# UVBoard.net
KiCad netlist of a schematic drawn in EAGLE
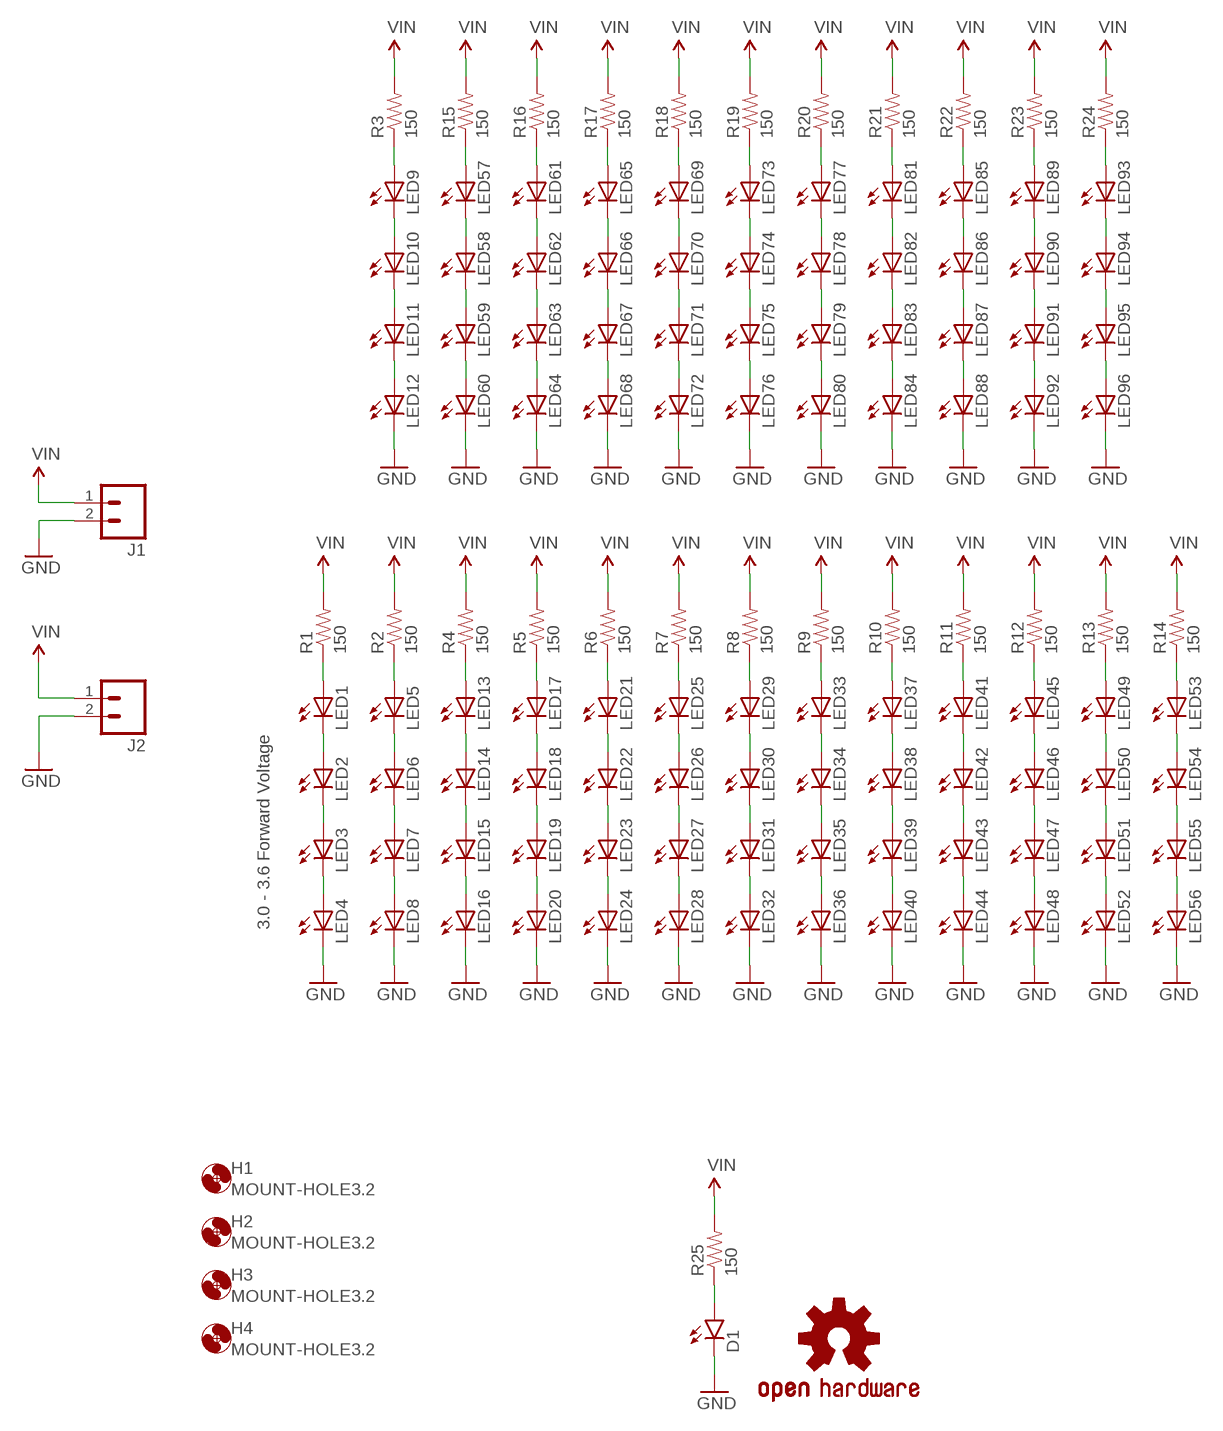
[diagram p0: schematic, sheet 1]

(export (version "E")
  (design (tool "Eeschema 10.0.6"))
  (components
    (comp (ref "D1")
      (value "LED1206-BOTTOM")
      (footprint "eagle-import:LED-1206-BOTTOM")
      (libsource (lib "eagle-import") (part "LED1206-BOTTOM"))
    )
    (comp (ref "H1")
      (value "MOUNT-HOLE3.2")
      (footprint "eagle-import:3,2")
      (libsource (lib "eagle-import") (part "MOUNT-HOLE3.2"))
    )
    (comp (ref "H2")
      (value "MOUNT-HOLE3.2")
      (footprint "eagle-import:3,2")
      (libsource (lib "eagle-import") (part "MOUNT-HOLE3.2"))
    )
    (comp (ref "H3")
      (value "MOUNT-HOLE3.2")
      (footprint "eagle-import:3,2")
      (libsource (lib "eagle-import") (part "MOUNT-HOLE3.2"))
    )
    (comp (ref "H4")
      (value "MOUNT-HOLE3.2")
      (footprint "eagle-import:3,2")
      (libsource (lib "eagle-import") (part "MOUNT-HOLE3.2"))
    )
    (comp (ref "J1")
      (value "M023.5MM")
      (footprint "eagle-import:SCREWTERMINAL-3.5MM-2")
      (libsource (lib "eagle-import") (part "M023.5MM"))
    )
    (comp (ref "J2")
      (value "M023.5MM")
      (footprint "eagle-import:SCREWTERMINAL-3.5MM-2")
      (libsource (lib "eagle-import") (part "M023.5MM"))
    )
    (comp (ref "LED1")
      (value "LEDP-LCC-2")
      (footprint "eagle-import:P-LCC-2")
      (libsource (lib "eagle-import") (part "LEDP-LCC-2"))
    )
    (comp (ref "LED2")
      (value "LEDP-LCC-2")
      (footprint "eagle-import:P-LCC-2")
      (libsource (lib "eagle-import") (part "LEDP-LCC-2"))
    )
    (comp (ref "LED3")
      (value "LEDP-LCC-2")
      (footprint "eagle-import:P-LCC-2")
      (libsource (lib "eagle-import") (part "LEDP-LCC-2"))
    )
    (comp (ref "LED4")
      (value "LEDP-LCC-2")
      (footprint "eagle-import:P-LCC-2")
      (libsource (lib "eagle-import") (part "LEDP-LCC-2"))
    )
    (comp (ref "LED5")
      (value "LEDP-LCC-2")
      (footprint "eagle-import:P-LCC-2")
      (libsource (lib "eagle-import") (part "LEDP-LCC-2"))
    )
    (comp (ref "LED6")
      (value "LEDP-LCC-2")
      (footprint "eagle-import:P-LCC-2")
      (libsource (lib "eagle-import") (part "LEDP-LCC-2"))
    )
    (comp (ref "LED7")
      (value "LEDP-LCC-2")
      (footprint "eagle-import:P-LCC-2")
      (libsource (lib "eagle-import") (part "LEDP-LCC-2"))
    )
    (comp (ref "LED8")
      (value "LEDP-LCC-2")
      (footprint "eagle-import:P-LCC-2")
      (libsource (lib "eagle-import") (part "LEDP-LCC-2"))
    )
    (comp (ref "LED9")
      (value "LEDP-LCC-2")
      (footprint "eagle-import:P-LCC-2")
      (libsource (lib "eagle-import") (part "LEDP-LCC-2"))
    )
    (comp (ref "LED10")
      (value "LEDP-LCC-2")
      (footprint "eagle-import:P-LCC-2")
      (libsource (lib "eagle-import") (part "LEDP-LCC-2"))
    )
    (comp (ref "LED11")
      (value "LEDP-LCC-2")
      (footprint "eagle-import:P-LCC-2")
      (libsource (lib "eagle-import") (part "LEDP-LCC-2"))
    )
    (comp (ref "LED12")
      (value "LEDP-LCC-2")
      (footprint "eagle-import:P-LCC-2")
      (libsource (lib "eagle-import") (part "LEDP-LCC-2"))
    )
    (comp (ref "LED13")
      (value "LEDP-LCC-2")
      (footprint "eagle-import:P-LCC-2")
      (libsource (lib "eagle-import") (part "LEDP-LCC-2"))
    )
    (comp (ref "LED14")
      (value "LEDP-LCC-2")
      (footprint "eagle-import:P-LCC-2")
      (libsource (lib "eagle-import") (part "LEDP-LCC-2"))
    )
    (comp (ref "LED15")
      (value "LEDP-LCC-2")
      (footprint "eagle-import:P-LCC-2")
      (libsource (lib "eagle-import") (part "LEDP-LCC-2"))
    )
    (comp (ref "LED16")
      (value "LEDP-LCC-2")
      (footprint "eagle-import:P-LCC-2")
      (libsource (lib "eagle-import") (part "LEDP-LCC-2"))
    )
    (comp (ref "LED17")
      (value "LEDP-LCC-2")
      (footprint "eagle-import:P-LCC-2")
      (libsource (lib "eagle-import") (part "LEDP-LCC-2"))
    )
    (comp (ref "LED18")
      (value "LEDP-LCC-2")
      (footprint "eagle-import:P-LCC-2")
      (libsource (lib "eagle-import") (part "LEDP-LCC-2"))
    )
    (comp (ref "LED19")
      (value "LEDP-LCC-2")
      (footprint "eagle-import:P-LCC-2")
      (libsource (lib "eagle-import") (part "LEDP-LCC-2"))
    )
    (comp (ref "LED20")
      (value "LEDP-LCC-2")
      (footprint "eagle-import:P-LCC-2")
      (libsource (lib "eagle-import") (part "LEDP-LCC-2"))
    )
    (comp (ref "LED21")
      (value "LEDP-LCC-2")
      (footprint "eagle-import:P-LCC-2")
      (libsource (lib "eagle-import") (part "LEDP-LCC-2"))
    )
    (comp (ref "LED22")
      (value "LEDP-LCC-2")
      (footprint "eagle-import:P-LCC-2")
      (libsource (lib "eagle-import") (part "LEDP-LCC-2"))
    )
    (comp (ref "LED23")
      (value "LEDP-LCC-2")
      (footprint "eagle-import:P-LCC-2")
      (libsource (lib "eagle-import") (part "LEDP-LCC-2"))
    )
    (comp (ref "LED24")
      (value "LEDP-LCC-2")
      (footprint "eagle-import:P-LCC-2")
      (libsource (lib "eagle-import") (part "LEDP-LCC-2"))
    )
    (comp (ref "LED25")
      (value "LEDP-LCC-2")
      (footprint "eagle-import:P-LCC-2")
      (libsource (lib "eagle-import") (part "LEDP-LCC-2"))
    )
    (comp (ref "LED26")
      (value "LEDP-LCC-2")
      (footprint "eagle-import:P-LCC-2")
      (libsource (lib "eagle-import") (part "LEDP-LCC-2"))
    )
    (comp (ref "LED27")
      (value "LEDP-LCC-2")
      (footprint "eagle-import:P-LCC-2")
      (libsource (lib "eagle-import") (part "LEDP-LCC-2"))
    )
    (comp (ref "LED28")
      (value "LEDP-LCC-2")
      (footprint "eagle-import:P-LCC-2")
      (libsource (lib "eagle-import") (part "LEDP-LCC-2"))
    )
    (comp (ref "LED29")
      (value "LEDP-LCC-2")
      (footprint "eagle-import:P-LCC-2")
      (libsource (lib "eagle-import") (part "LEDP-LCC-2"))
    )
    (comp (ref "LED30")
      (value "LEDP-LCC-2")
      (footprint "eagle-import:P-LCC-2")
      (libsource (lib "eagle-import") (part "LEDP-LCC-2"))
    )
    (comp (ref "LED31")
      (value "LEDP-LCC-2")
      (footprint "eagle-import:P-LCC-2")
      (libsource (lib "eagle-import") (part "LEDP-LCC-2"))
    )
    (comp (ref "LED32")
      (value "LEDP-LCC-2")
      (footprint "eagle-import:P-LCC-2")
      (libsource (lib "eagle-import") (part "LEDP-LCC-2"))
    )
    (comp (ref "LED33")
      (value "LEDP-LCC-2")
      (footprint "eagle-import:P-LCC-2")
      (libsource (lib "eagle-import") (part "LEDP-LCC-2"))
    )
    (comp (ref "LED34")
      (value "LEDP-LCC-2")
      (footprint "eagle-import:P-LCC-2")
      (libsource (lib "eagle-import") (part "LEDP-LCC-2"))
    )
    (comp (ref "LED35")
      (value "LEDP-LCC-2")
      (footprint "eagle-import:P-LCC-2")
      (libsource (lib "eagle-import") (part "LEDP-LCC-2"))
    )
    (comp (ref "LED36")
      (value "LEDP-LCC-2")
      (footprint "eagle-import:P-LCC-2")
      (libsource (lib "eagle-import") (part "LEDP-LCC-2"))
    )
    (comp (ref "LED37")
      (value "LEDP-LCC-2")
      (footprint "eagle-import:P-LCC-2")
      (libsource (lib "eagle-import") (part "LEDP-LCC-2"))
    )
    (comp (ref "LED38")
      (value "LEDP-LCC-2")
      (footprint "eagle-import:P-LCC-2")
      (libsource (lib "eagle-import") (part "LEDP-LCC-2"))
    )
    (comp (ref "LED39")
      (value "LEDP-LCC-2")
      (footprint "eagle-import:P-LCC-2")
      (libsource (lib "eagle-import") (part "LEDP-LCC-2"))
    )
    (comp (ref "LED40")
      (value "LEDP-LCC-2")
      (footprint "eagle-import:P-LCC-2")
      (libsource (lib "eagle-import") (part "LEDP-LCC-2"))
    )
    (comp (ref "LED41")
      (value "LEDP-LCC-2")
      (footprint "eagle-import:P-LCC-2")
      (libsource (lib "eagle-import") (part "LEDP-LCC-2"))
    )
    (comp (ref "LED42")
      (value "LEDP-LCC-2")
      (footprint "eagle-import:P-LCC-2")
      (libsource (lib "eagle-import") (part "LEDP-LCC-2"))
    )
    (comp (ref "LED43")
      (value "LEDP-LCC-2")
      (footprint "eagle-import:P-LCC-2")
      (libsource (lib "eagle-import") (part "LEDP-LCC-2"))
    )
    (comp (ref "LED44")
      (value "LEDP-LCC-2")
      (footprint "eagle-import:P-LCC-2")
      (libsource (lib "eagle-import") (part "LEDP-LCC-2"))
    )
    (comp (ref "LED45")
      (value "LEDP-LCC-2")
      (footprint "eagle-import:P-LCC-2")
      (libsource (lib "eagle-import") (part "LEDP-LCC-2"))
    )
    (comp (ref "LED46")
      (value "LEDP-LCC-2")
      (footprint "eagle-import:P-LCC-2")
      (libsource (lib "eagle-import") (part "LEDP-LCC-2"))
    )
    (comp (ref "LED47")
      (value "LEDP-LCC-2")
      (footprint "eagle-import:P-LCC-2")
      (libsource (lib "eagle-import") (part "LEDP-LCC-2"))
    )
    (comp (ref "LED48")
      (value "LEDP-LCC-2")
      (footprint "eagle-import:P-LCC-2")
      (libsource (lib "eagle-import") (part "LEDP-LCC-2"))
    )
    (comp (ref "LED49")
      (value "LEDP-LCC-2")
      (footprint "eagle-import:P-LCC-2")
      (libsource (lib "eagle-import") (part "LEDP-LCC-2"))
    )
    (comp (ref "LED50")
      (value "LEDP-LCC-2")
      (footprint "eagle-import:P-LCC-2")
      (libsource (lib "eagle-import") (part "LEDP-LCC-2"))
    )
    (comp (ref "LED51")
      (value "LEDP-LCC-2")
      (footprint "eagle-import:P-LCC-2")
      (libsource (lib "eagle-import") (part "LEDP-LCC-2"))
    )
    (comp (ref "LED52")
      (value "LEDP-LCC-2")
      (footprint "eagle-import:P-LCC-2")
      (libsource (lib "eagle-import") (part "LEDP-LCC-2"))
    )
    (comp (ref "LED53")
      (value "LEDP-LCC-2")
      (footprint "eagle-import:P-LCC-2")
      (libsource (lib "eagle-import") (part "LEDP-LCC-2"))
    )
    (comp (ref "LED54")
      (value "LEDP-LCC-2")
      (footprint "eagle-import:P-LCC-2")
      (libsource (lib "eagle-import") (part "LEDP-LCC-2"))
    )
    (comp (ref "LED55")
      (value "LEDP-LCC-2")
      (footprint "eagle-import:P-LCC-2")
      (libsource (lib "eagle-import") (part "LEDP-LCC-2"))
    )
    (comp (ref "LED56")
      (value "LEDP-LCC-2")
      (footprint "eagle-import:P-LCC-2")
      (libsource (lib "eagle-import") (part "LEDP-LCC-2"))
    )
    (comp (ref "LED57")
      (value "LEDP-LCC-2")
      (footprint "eagle-import:P-LCC-2")
      (libsource (lib "eagle-import") (part "LEDP-LCC-2"))
    )
    (comp (ref "LED58")
      (value "LEDP-LCC-2")
      (footprint "eagle-import:P-LCC-2")
      (libsource (lib "eagle-import") (part "LEDP-LCC-2"))
    )
    (comp (ref "LED59")
      (value "LEDP-LCC-2")
      (footprint "eagle-import:P-LCC-2")
      (libsource (lib "eagle-import") (part "LEDP-LCC-2"))
    )
    (comp (ref "LED60")
      (value "LEDP-LCC-2")
      (footprint "eagle-import:P-LCC-2")
      (libsource (lib "eagle-import") (part "LEDP-LCC-2"))
    )
    (comp (ref "LED61")
      (value "LEDP-LCC-2")
      (footprint "eagle-import:P-LCC-2")
      (libsource (lib "eagle-import") (part "LEDP-LCC-2"))
    )
    (comp (ref "LED62")
      (value "LEDP-LCC-2")
      (footprint "eagle-import:P-LCC-2")
      (libsource (lib "eagle-import") (part "LEDP-LCC-2"))
    )
    (comp (ref "LED63")
      (value "LEDP-LCC-2")
      (footprint "eagle-import:P-LCC-2")
      (libsource (lib "eagle-import") (part "LEDP-LCC-2"))
    )
    (comp (ref "LED64")
      (value "LEDP-LCC-2")
      (footprint "eagle-import:P-LCC-2")
      (libsource (lib "eagle-import") (part "LEDP-LCC-2"))
    )
    (comp (ref "LED65")
      (value "LEDP-LCC-2")
      (footprint "eagle-import:P-LCC-2")
      (libsource (lib "eagle-import") (part "LEDP-LCC-2"))
    )
    (comp (ref "LED66")
      (value "LEDP-LCC-2")
      (footprint "eagle-import:P-LCC-2")
      (libsource (lib "eagle-import") (part "LEDP-LCC-2"))
    )
    (comp (ref "LED67")
      (value "LEDP-LCC-2")
      (footprint "eagle-import:P-LCC-2")
      (libsource (lib "eagle-import") (part "LEDP-LCC-2"))
    )
    (comp (ref "LED68")
      (value "LEDP-LCC-2")
      (footprint "eagle-import:P-LCC-2")
      (libsource (lib "eagle-import") (part "LEDP-LCC-2"))
    )
    (comp (ref "LED69")
      (value "LEDP-LCC-2")
      (footprint "eagle-import:P-LCC-2")
      (libsource (lib "eagle-import") (part "LEDP-LCC-2"))
    )
    (comp (ref "LED70")
      (value "LEDP-LCC-2")
      (footprint "eagle-import:P-LCC-2")
      (libsource (lib "eagle-import") (part "LEDP-LCC-2"))
    )
    (comp (ref "LED71")
      (value "LEDP-LCC-2")
      (footprint "eagle-import:P-LCC-2")
      (libsource (lib "eagle-import") (part "LEDP-LCC-2"))
    )
    (comp (ref "LED72")
      (value "LEDP-LCC-2")
      (footprint "eagle-import:P-LCC-2")
      (libsource (lib "eagle-import") (part "LEDP-LCC-2"))
    )
    (comp (ref "LED73")
      (value "LEDP-LCC-2")
      (footprint "eagle-import:P-LCC-2")
      (libsource (lib "eagle-import") (part "LEDP-LCC-2"))
    )
    (comp (ref "LED74")
      (value "LEDP-LCC-2")
      (footprint "eagle-import:P-LCC-2")
      (libsource (lib "eagle-import") (part "LEDP-LCC-2"))
    )
    (comp (ref "LED75")
      (value "LEDP-LCC-2")
      (footprint "eagle-import:P-LCC-2")
      (libsource (lib "eagle-import") (part "LEDP-LCC-2"))
    )
    (comp (ref "LED76")
      (value "LEDP-LCC-2")
      (footprint "eagle-import:P-LCC-2")
      (libsource (lib "eagle-import") (part "LEDP-LCC-2"))
    )
    (comp (ref "LED77")
      (value "LEDP-LCC-2")
      (footprint "eagle-import:P-LCC-2")
      (libsource (lib "eagle-import") (part "LEDP-LCC-2"))
    )
    (comp (ref "LED78")
      (value "LEDP-LCC-2")
      (footprint "eagle-import:P-LCC-2")
      (libsource (lib "eagle-import") (part "LEDP-LCC-2"))
    )
    (comp (ref "LED79")
      (value "LEDP-LCC-2")
      (footprint "eagle-import:P-LCC-2")
      (libsource (lib "eagle-import") (part "LEDP-LCC-2"))
    )
    (comp (ref "LED80")
      (value "LEDP-LCC-2")
      (footprint "eagle-import:P-LCC-2")
      (libsource (lib "eagle-import") (part "LEDP-LCC-2"))
    )
    (comp (ref "LED81")
      (value "LEDP-LCC-2")
      (footprint "eagle-import:P-LCC-2")
      (libsource (lib "eagle-import") (part "LEDP-LCC-2"))
    )
    (comp (ref "LED82")
      (value "LEDP-LCC-2")
      (footprint "eagle-import:P-LCC-2")
      (libsource (lib "eagle-import") (part "LEDP-LCC-2"))
    )
    (comp (ref "LED83")
      (value "LEDP-LCC-2")
      (footprint "eagle-import:P-LCC-2")
      (libsource (lib "eagle-import") (part "LEDP-LCC-2"))
    )
    (comp (ref "LED84")
      (value "LEDP-LCC-2")
      (footprint "eagle-import:P-LCC-2")
      (libsource (lib "eagle-import") (part "LEDP-LCC-2"))
    )
    (comp (ref "LED85")
      (value "LEDP-LCC-2")
      (footprint "eagle-import:P-LCC-2")
      (libsource (lib "eagle-import") (part "LEDP-LCC-2"))
    )
    (comp (ref "LED86")
      (value "LEDP-LCC-2")
      (footprint "eagle-import:P-LCC-2")
      (libsource (lib "eagle-import") (part "LEDP-LCC-2"))
    )
    (comp (ref "LED87")
      (value "LEDP-LCC-2")
      (footprint "eagle-import:P-LCC-2")
      (libsource (lib "eagle-import") (part "LEDP-LCC-2"))
    )
    (comp (ref "LED88")
      (value "LEDP-LCC-2")
      (footprint "eagle-import:P-LCC-2")
      (libsource (lib "eagle-import") (part "LEDP-LCC-2"))
    )
    (comp (ref "LED89")
      (value "LEDP-LCC-2")
      (footprint "eagle-import:P-LCC-2")
      (libsource (lib "eagle-import") (part "LEDP-LCC-2"))
    )
    (comp (ref "LED90")
      (value "LEDP-LCC-2")
      (footprint "eagle-import:P-LCC-2")
      (libsource (lib "eagle-import") (part "LEDP-LCC-2"))
    )
    (comp (ref "LED91")
      (value "LEDP-LCC-2")
      (footprint "eagle-import:P-LCC-2")
      (libsource (lib "eagle-import") (part "LEDP-LCC-2"))
    )
    (comp (ref "LED92")
      (value "LEDP-LCC-2")
      (footprint "eagle-import:P-LCC-2")
      (libsource (lib "eagle-import") (part "LEDP-LCC-2"))
    )
    (comp (ref "LED93")
      (value "LEDP-LCC-2")
      (footprint "eagle-import:P-LCC-2")
      (libsource (lib "eagle-import") (part "LEDP-LCC-2"))
    )
    (comp (ref "LED94")
      (value "LEDP-LCC-2")
      (footprint "eagle-import:P-LCC-2")
      (libsource (lib "eagle-import") (part "LEDP-LCC-2"))
    )
    (comp (ref "LED95")
      (value "LEDP-LCC-2")
      (footprint "eagle-import:P-LCC-2")
      (libsource (lib "eagle-import") (part "LEDP-LCC-2"))
    )
    (comp (ref "LED96")
      (value "LEDP-LCC-2")
      (footprint "eagle-import:P-LCC-2")
      (libsource (lib "eagle-import") (part "LEDP-LCC-2"))
    )
    (comp (ref "LOGO1")
      (value "OSHW-LOGOM")
      (footprint "eagle-import:OSHW-LOGO-M")
      (libsource (lib "eagle-import") (part "OSHW-LOGOM"))
    )
    (comp (ref "R1")
      (value "150")
      (footprint "eagle-import:1206")
      (libsource (lib "eagle-import") (part "RESISTOR1206"))
    )
    (comp (ref "R2")
      (value "150")
      (footprint "eagle-import:1206")
      (libsource (lib "eagle-import") (part "RESISTOR1206"))
    )
    (comp (ref "R3")
      (value "150")
      (footprint "eagle-import:1206")
      (libsource (lib "eagle-import") (part "RESISTOR1206"))
    )
    (comp (ref "R4")
      (value "150")
      (footprint "eagle-import:1206")
      (libsource (lib "eagle-import") (part "RESISTOR1206"))
    )
    (comp (ref "R5")
      (value "150")
      (footprint "eagle-import:1206")
      (libsource (lib "eagle-import") (part "RESISTOR1206"))
    )
    (comp (ref "R6")
      (value "150")
      (footprint "eagle-import:1206")
      (libsource (lib "eagle-import") (part "RESISTOR1206"))
    )
    (comp (ref "R7")
      (value "150")
      (footprint "eagle-import:1206")
      (libsource (lib "eagle-import") (part "RESISTOR1206"))
    )
    (comp (ref "R8")
      (value "150")
      (footprint "eagle-import:1206")
      (libsource (lib "eagle-import") (part "RESISTOR1206"))
    )
    (comp (ref "R9")
      (value "150")
      (footprint "eagle-import:1206")
      (libsource (lib "eagle-import") (part "RESISTOR1206"))
    )
    (comp (ref "R10")
      (value "150")
      (footprint "eagle-import:1206")
      (libsource (lib "eagle-import") (part "RESISTOR1206"))
    )
    (comp (ref "R11")
      (value "150")
      (footprint "eagle-import:1206")
      (libsource (lib "eagle-import") (part "RESISTOR1206"))
    )
    (comp (ref "R12")
      (value "150")
      (footprint "eagle-import:1206")
      (libsource (lib "eagle-import") (part "RESISTOR1206"))
    )
    (comp (ref "R13")
      (value "150")
      (footprint "eagle-import:1206")
      (libsource (lib "eagle-import") (part "RESISTOR1206"))
    )
    (comp (ref "R14")
      (value "150")
      (footprint "eagle-import:1206")
      (libsource (lib "eagle-import") (part "RESISTOR1206"))
    )
    (comp (ref "R15")
      (value "150")
      (footprint "eagle-import:1206")
      (libsource (lib "eagle-import") (part "RESISTOR1206"))
    )
    (comp (ref "R16")
      (value "150")
      (footprint "eagle-import:1206")
      (libsource (lib "eagle-import") (part "RESISTOR1206"))
    )
    (comp (ref "R17")
      (value "150")
      (footprint "eagle-import:1206")
      (libsource (lib "eagle-import") (part "RESISTOR1206"))
    )
    (comp (ref "R18")
      (value "150")
      (footprint "eagle-import:1206")
      (libsource (lib "eagle-import") (part "RESISTOR1206"))
    )
    (comp (ref "R19")
      (value "150")
      (footprint "eagle-import:1206")
      (libsource (lib "eagle-import") (part "RESISTOR1206"))
    )
    (comp (ref "R20")
      (value "150")
      (footprint "eagle-import:1206")
      (libsource (lib "eagle-import") (part "RESISTOR1206"))
    )
    (comp (ref "R21")
      (value "150")
      (footprint "eagle-import:1206")
      (libsource (lib "eagle-import") (part "RESISTOR1206"))
    )
    (comp (ref "R22")
      (value "150")
      (footprint "eagle-import:1206")
      (libsource (lib "eagle-import") (part "RESISTOR1206"))
    )
    (comp (ref "R23")
      (value "150")
      (footprint "eagle-import:1206")
      (libsource (lib "eagle-import") (part "RESISTOR1206"))
    )
    (comp (ref "R24")
      (value "150")
      (footprint "eagle-import:1206")
      (libsource (lib "eagle-import") (part "RESISTOR1206"))
    )
    (comp (ref "R25")
      (value "150")
      (footprint "eagle-import:1206")
      (libsource (lib "eagle-import") (part "RESISTOR1206"))
    )
  )
  (nets
    (net (code "1") (name "GND") (class "Default")
      (node (ref "D1") (pin "C") (pinfunction "C_C") (pintype "passive"))
      (node (ref "J1") (pin "2") (pinfunction "2_2") (pintype "passive"))
      (node (ref "J2") (pin "2") (pinfunction "2_2") (pintype "passive"))
      (node (ref "LED12") (pin "C") (pinfunction "C_C") (pintype "passive"))
      (node (ref "LED16") (pin "C") (pinfunction "C_C") (pintype "passive"))
      (node (ref "LED20") (pin "C") (pinfunction "C_C") (pintype "passive"))
      (node (ref "LED24") (pin "C") (pinfunction "C_C") (pintype "passive"))
      (node (ref "LED28") (pin "C") (pinfunction "C_C") (pintype "passive"))
      (node (ref "LED32") (pin "C") (pinfunction "C_C") (pintype "passive"))
      (node (ref "LED36") (pin "C") (pinfunction "C_C") (pintype "passive"))
      (node (ref "LED4") (pin "C") (pinfunction "C_C") (pintype "passive"))
      (node (ref "LED40") (pin "C") (pinfunction "C_C") (pintype "passive"))
      (node (ref "LED44") (pin "C") (pinfunction "C_C") (pintype "passive"))
      (node (ref "LED48") (pin "C") (pinfunction "C_C") (pintype "passive"))
      (node (ref "LED52") (pin "C") (pinfunction "C_C") (pintype "passive"))
      (node (ref "LED56") (pin "C") (pinfunction "C_C") (pintype "passive"))
      (node (ref "LED60") (pin "C") (pinfunction "C_C") (pintype "passive"))
      (node (ref "LED64") (pin "C") (pinfunction "C_C") (pintype "passive"))
      (node (ref "LED68") (pin "C") (pinfunction "C_C") (pintype "passive"))
      (node (ref "LED72") (pin "C") (pinfunction "C_C") (pintype "passive"))
      (node (ref "LED76") (pin "C") (pinfunction "C_C") (pintype "passive"))
      (node (ref "LED8") (pin "C") (pinfunction "C_C") (pintype "passive"))
      (node (ref "LED80") (pin "C") (pinfunction "C_C") (pintype "passive"))
      (node (ref "LED84") (pin "C") (pinfunction "C_C") (pintype "passive"))
      (node (ref "LED88") (pin "C") (pinfunction "C_C") (pintype "passive"))
      (node (ref "LED92") (pin "C") (pinfunction "C_C") (pintype "passive"))
      (node (ref "LED96") (pin "C") (pinfunction "C_C") (pintype "passive"))
    )
    (net (code "2") (name "Net-(D1-PadA)") (class "Default")
      (node (ref "D1") (pin "A") (pinfunction "A_A") (pintype "passive"))
      (node (ref "R25") (pin "1") (pinfunction "1_1") (pintype "passive"))
    )
    (net (code "3") (name "Net-(LED1-PadA)") (class "Default")
      (node (ref "LED1") (pin "A") (pinfunction "A_A") (pintype "passive"))
      (node (ref "R1") (pin "1") (pinfunction "1_1") (pintype "passive"))
    )
    (net (code "4") (name "Net-(LED1-PadC)") (class "Default")
      (node (ref "LED1") (pin "C") (pinfunction "C_C") (pintype "passive"))
      (node (ref "LED2") (pin "A") (pinfunction "A_A") (pintype "passive"))
    )
    (net (code "5") (name "Net-(LED2-PadC)") (class "Default")
      (node (ref "LED2") (pin "C") (pinfunction "C_C") (pintype "passive"))
      (node (ref "LED3") (pin "A") (pinfunction "A_A") (pintype "passive"))
    )
    (net (code "6") (name "Net-(LED3-PadC)") (class "Default")
      (node (ref "LED3") (pin "C") (pinfunction "C_C") (pintype "passive"))
      (node (ref "LED4") (pin "A") (pinfunction "A_A") (pintype "passive"))
    )
    (net (code "7") (name "Net-(LED5-PadA)") (class "Default")
      (node (ref "LED5") (pin "A") (pinfunction "A_A") (pintype "passive"))
      (node (ref "R2") (pin "1") (pinfunction "1_1") (pintype "passive"))
    )
    (net (code "8") (name "Net-(LED5-PadC)") (class "Default")
      (node (ref "LED5") (pin "C") (pinfunction "C_C") (pintype "passive"))
      (node (ref "LED6") (pin "A") (pinfunction "A_A") (pintype "passive"))
    )
    (net (code "9") (name "Net-(LED6-PadC)") (class "Default")
      (node (ref "LED6") (pin "C") (pinfunction "C_C") (pintype "passive"))
      (node (ref "LED7") (pin "A") (pinfunction "A_A") (pintype "passive"))
    )
    (net (code "10") (name "Net-(LED7-PadC)") (class "Default")
      (node (ref "LED7") (pin "C") (pinfunction "C_C") (pintype "passive"))
      (node (ref "LED8") (pin "A") (pinfunction "A_A") (pintype "passive"))
    )
    (net (code "11") (name "Net-(LED9-PadA)") (class "Default")
      (node (ref "LED9") (pin "A") (pinfunction "A_A") (pintype "passive"))
      (node (ref "R3") (pin "1") (pinfunction "1_1") (pintype "passive"))
    )
    (net (code "12") (name "Net-(LED10-PadA)") (class "Default")
      (node (ref "LED10") (pin "A") (pinfunction "A_A") (pintype "passive"))
      (node (ref "LED9") (pin "C") (pinfunction "C_C") (pintype "passive"))
    )
    (net (code "13") (name "Net-(LED10-PadC)") (class "Default")
      (node (ref "LED10") (pin "C") (pinfunction "C_C") (pintype "passive"))
      (node (ref "LED11") (pin "A") (pinfunction "A_A") (pintype "passive"))
    )
    (net (code "14") (name "Net-(LED11-PadC)") (class "Default")
      (node (ref "LED11") (pin "C") (pinfunction "C_C") (pintype "passive"))
      (node (ref "LED12") (pin "A") (pinfunction "A_A") (pintype "passive"))
    )
    (net (code "15") (name "Net-(LED13-PadA)") (class "Default")
      (node (ref "LED13") (pin "A") (pinfunction "A_A") (pintype "passive"))
      (node (ref "R4") (pin "1") (pinfunction "1_1") (pintype "passive"))
    )
    (net (code "16") (name "Net-(LED13-PadC)") (class "Default")
      (node (ref "LED13") (pin "C") (pinfunction "C_C") (pintype "passive"))
      (node (ref "LED14") (pin "A") (pinfunction "A_A") (pintype "passive"))
    )
    (net (code "17") (name "Net-(LED14-PadC)") (class "Default")
      (node (ref "LED14") (pin "C") (pinfunction "C_C") (pintype "passive"))
      (node (ref "LED15") (pin "A") (pinfunction "A_A") (pintype "passive"))
    )
    (net (code "18") (name "Net-(LED15-PadC)") (class "Default")
      (node (ref "LED15") (pin "C") (pinfunction "C_C") (pintype "passive"))
      (node (ref "LED16") (pin "A") (pinfunction "A_A") (pintype "passive"))
    )
    (net (code "19") (name "Net-(LED17-PadA)") (class "Default")
      (node (ref "LED17") (pin "A") (pinfunction "A_A") (pintype "passive"))
      (node (ref "R5") (pin "1") (pinfunction "1_1") (pintype "passive"))
    )
    (net (code "20") (name "Net-(LED17-PadC)") (class "Default")
      (node (ref "LED17") (pin "C") (pinfunction "C_C") (pintype "passive"))
      (node (ref "LED18") (pin "A") (pinfunction "A_A") (pintype "passive"))
    )
    (net (code "21") (name "Net-(LED18-PadC)") (class "Default")
      (node (ref "LED18") (pin "C") (pinfunction "C_C") (pintype "passive"))
      (node (ref "LED19") (pin "A") (pinfunction "A_A") (pintype "passive"))
    )
    (net (code "22") (name "Net-(LED19-PadC)") (class "Default")
      (node (ref "LED19") (pin "C") (pinfunction "C_C") (pintype "passive"))
      (node (ref "LED20") (pin "A") (pinfunction "A_A") (pintype "passive"))
    )
    (net (code "23") (name "Net-(LED21-PadA)") (class "Default")
      (node (ref "LED21") (pin "A") (pinfunction "A_A") (pintype "passive"))
      (node (ref "R6") (pin "1") (pinfunction "1_1") (pintype "passive"))
    )
    (net (code "24") (name "Net-(LED21-PadC)") (class "Default")
      (node (ref "LED21") (pin "C") (pinfunction "C_C") (pintype "passive"))
      (node (ref "LED22") (pin "A") (pinfunction "A_A") (pintype "passive"))
    )
    (net (code "25") (name "Net-(LED22-PadC)") (class "Default")
      (node (ref "LED22") (pin "C") (pinfunction "C_C") (pintype "passive"))
      (node (ref "LED23") (pin "A") (pinfunction "A_A") (pintype "passive"))
    )
    (net (code "26") (name "Net-(LED23-PadC)") (class "Default")
      (node (ref "LED23") (pin "C") (pinfunction "C_C") (pintype "passive"))
      (node (ref "LED24") (pin "A") (pinfunction "A_A") (pintype "passive"))
    )
    (net (code "27") (name "Net-(LED25-PadA)") (class "Default")
      (node (ref "LED25") (pin "A") (pinfunction "A_A") (pintype "passive"))
      (node (ref "R7") (pin "1") (pinfunction "1_1") (pintype "passive"))
    )
    (net (code "28") (name "Net-(LED25-PadC)") (class "Default")
      (node (ref "LED25") (pin "C") (pinfunction "C_C") (pintype "passive"))
      (node (ref "LED26") (pin "A") (pinfunction "A_A") (pintype "passive"))
    )
    (net (code "29") (name "Net-(LED26-PadC)") (class "Default")
      (node (ref "LED26") (pin "C") (pinfunction "C_C") (pintype "passive"))
      (node (ref "LED27") (pin "A") (pinfunction "A_A") (pintype "passive"))
    )
    (net (code "30") (name "Net-(LED27-PadC)") (class "Default")
      (node (ref "LED27") (pin "C") (pinfunction "C_C") (pintype "passive"))
      (node (ref "LED28") (pin "A") (pinfunction "A_A") (pintype "passive"))
    )
    (net (code "31") (name "Net-(LED29-PadA)") (class "Default")
      (node (ref "LED29") (pin "A") (pinfunction "A_A") (pintype "passive"))
      (node (ref "R8") (pin "1") (pinfunction "1_1") (pintype "passive"))
    )
    (net (code "32") (name "Net-(LED29-PadC)") (class "Default")
      (node (ref "LED29") (pin "C") (pinfunction "C_C") (pintype "passive"))
      (node (ref "LED30") (pin "A") (pinfunction "A_A") (pintype "passive"))
    )
    (net (code "33") (name "Net-(LED30-PadC)") (class "Default")
      (node (ref "LED30") (pin "C") (pinfunction "C_C") (pintype "passive"))
      (node (ref "LED31") (pin "A") (pinfunction "A_A") (pintype "passive"))
    )
    (net (code "34") (name "Net-(LED31-PadC)") (class "Default")
      (node (ref "LED31") (pin "C") (pinfunction "C_C") (pintype "passive"))
      (node (ref "LED32") (pin "A") (pinfunction "A_A") (pintype "passive"))
    )
    (net (code "35") (name "Net-(LED33-PadA)") (class "Default")
      (node (ref "LED33") (pin "A") (pinfunction "A_A") (pintype "passive"))
      (node (ref "R9") (pin "1") (pinfunction "1_1") (pintype "passive"))
    )
    (net (code "36") (name "Net-(LED33-PadC)") (class "Default")
      (node (ref "LED33") (pin "C") (pinfunction "C_C") (pintype "passive"))
      (node (ref "LED34") (pin "A") (pinfunction "A_A") (pintype "passive"))
    )
    (net (code "37") (name "Net-(LED34-PadC)") (class "Default")
      (node (ref "LED34") (pin "C") (pinfunction "C_C") (pintype "passive"))
      (node (ref "LED35") (pin "A") (pinfunction "A_A") (pintype "passive"))
    )
    (net (code "38") (name "Net-(LED35-PadC)") (class "Default")
      (node (ref "LED35") (pin "C") (pinfunction "C_C") (pintype "passive"))
      (node (ref "LED36") (pin "A") (pinfunction "A_A") (pintype "passive"))
    )
    (net (code "39") (name "Net-(LED37-PadA)") (class "Default")
      (node (ref "LED37") (pin "A") (pinfunction "A_A") (pintype "passive"))
      (node (ref "R10") (pin "1") (pinfunction "1_1") (pintype "passive"))
    )
    (net (code "40") (name "Net-(LED37-PadC)") (class "Default")
      (node (ref "LED37") (pin "C") (pinfunction "C_C") (pintype "passive"))
      (node (ref "LED38") (pin "A") (pinfunction "A_A") (pintype "passive"))
    )
    (net (code "41") (name "Net-(LED38-PadC)") (class "Default")
      (node (ref "LED38") (pin "C") (pinfunction "C_C") (pintype "passive"))
      (node (ref "LED39") (pin "A") (pinfunction "A_A") (pintype "passive"))
    )
    (net (code "42") (name "Net-(LED39-PadC)") (class "Default")
      (node (ref "LED39") (pin "C") (pinfunction "C_C") (pintype "passive"))
      (node (ref "LED40") (pin "A") (pinfunction "A_A") (pintype "passive"))
    )
    (net (code "43") (name "Net-(LED41-PadA)") (class "Default")
      (node (ref "LED41") (pin "A") (pinfunction "A_A") (pintype "passive"))
      (node (ref "R11") (pin "1") (pinfunction "1_1") (pintype "passive"))
    )
    (net (code "44") (name "Net-(LED41-PadC)") (class "Default")
      (node (ref "LED41") (pin "C") (pinfunction "C_C") (pintype "passive"))
      (node (ref "LED42") (pin "A") (pinfunction "A_A") (pintype "passive"))
    )
    (net (code "45") (name "Net-(LED42-PadC)") (class "Default")
      (node (ref "LED42") (pin "C") (pinfunction "C_C") (pintype "passive"))
      (node (ref "LED43") (pin "A") (pinfunction "A_A") (pintype "passive"))
    )
    (net (code "46") (name "Net-(LED43-PadC)") (class "Default")
      (node (ref "LED43") (pin "C") (pinfunction "C_C") (pintype "passive"))
      (node (ref "LED44") (pin "A") (pinfunction "A_A") (pintype "passive"))
    )
    (net (code "47") (name "Net-(LED45-PadA)") (class "Default")
      (node (ref "LED45") (pin "A") (pinfunction "A_A") (pintype "passive"))
      (node (ref "R12") (pin "1") (pinfunction "1_1") (pintype "passive"))
    )
    (net (code "48") (name "Net-(LED45-PadC)") (class "Default")
      (node (ref "LED45") (pin "C") (pinfunction "C_C") (pintype "passive"))
      (node (ref "LED46") (pin "A") (pinfunction "A_A") (pintype "passive"))
    )
    (net (code "49") (name "Net-(LED46-PadC)") (class "Default")
      (node (ref "LED46") (pin "C") (pinfunction "C_C") (pintype "passive"))
      (node (ref "LED47") (pin "A") (pinfunction "A_A") (pintype "passive"))
    )
    (net (code "50") (name "Net-(LED47-PadC)") (class "Default")
      (node (ref "LED47") (pin "C") (pinfunction "C_C") (pintype "passive"))
      (node (ref "LED48") (pin "A") (pinfunction "A_A") (pintype "passive"))
    )
    (net (code "51") (name "Net-(LED49-PadA)") (class "Default")
      (node (ref "LED49") (pin "A") (pinfunction "A_A") (pintype "passive"))
      (node (ref "R13") (pin "1") (pinfunction "1_1") (pintype "passive"))
    )
    (net (code "52") (name "Net-(LED49-PadC)") (class "Default")
      (node (ref "LED49") (pin "C") (pinfunction "C_C") (pintype "passive"))
      (node (ref "LED50") (pin "A") (pinfunction "A_A") (pintype "passive"))
    )
    (net (code "53") (name "Net-(LED50-PadC)") (class "Default")
      (node (ref "LED50") (pin "C") (pinfunction "C_C") (pintype "passive"))
      (node (ref "LED51") (pin "A") (pinfunction "A_A") (pintype "passive"))
    )
    (net (code "54") (name "Net-(LED51-PadC)") (class "Default")
      (node (ref "LED51") (pin "C") (pinfunction "C_C") (pintype "passive"))
      (node (ref "LED52") (pin "A") (pinfunction "A_A") (pintype "passive"))
    )
    (net (code "55") (name "Net-(LED53-PadA)") (class "Default")
      (node (ref "LED53") (pin "A") (pinfunction "A_A") (pintype "passive"))
      (node (ref "R14") (pin "1") (pinfunction "1_1") (pintype "passive"))
    )
    (net (code "56") (name "Net-(LED53-PadC)") (class "Default")
      (node (ref "LED53") (pin "C") (pinfunction "C_C") (pintype "passive"))
      (node (ref "LED54") (pin "A") (pinfunction "A_A") (pintype "passive"))
    )
    (net (code "57") (name "Net-(LED54-PadC)") (class "Default")
      (node (ref "LED54") (pin "C") (pinfunction "C_C") (pintype "passive"))
      (node (ref "LED55") (pin "A") (pinfunction "A_A") (pintype "passive"))
    )
    (net (code "58") (name "Net-(LED55-PadC)") (class "Default")
      (node (ref "LED55") (pin "C") (pinfunction "C_C") (pintype "passive"))
      (node (ref "LED56") (pin "A") (pinfunction "A_A") (pintype "passive"))
    )
    (net (code "59") (name "Net-(LED57-PadA)") (class "Default")
      (node (ref "LED57") (pin "A") (pinfunction "A_A") (pintype "passive"))
      (node (ref "R15") (pin "1") (pinfunction "1_1") (pintype "passive"))
    )
    (net (code "60") (name "Net-(LED57-PadC)") (class "Default")
      (node (ref "LED57") (pin "C") (pinfunction "C_C") (pintype "passive"))
      (node (ref "LED58") (pin "A") (pinfunction "A_A") (pintype "passive"))
    )
    (net (code "61") (name "Net-(LED58-PadC)") (class "Default")
      (node (ref "LED58") (pin "C") (pinfunction "C_C") (pintype "passive"))
      (node (ref "LED59") (pin "A") (pinfunction "A_A") (pintype "passive"))
    )
    (net (code "62") (name "Net-(LED59-PadC)") (class "Default")
      (node (ref "LED59") (pin "C") (pinfunction "C_C") (pintype "passive"))
      (node (ref "LED60") (pin "A") (pinfunction "A_A") (pintype "passive"))
    )
    (net (code "63") (name "Net-(LED61-PadA)") (class "Default")
      (node (ref "LED61") (pin "A") (pinfunction "A_A") (pintype "passive"))
      (node (ref "R16") (pin "1") (pinfunction "1_1") (pintype "passive"))
    )
    (net (code "64") (name "Net-(LED61-PadC)") (class "Default")
      (node (ref "LED61") (pin "C") (pinfunction "C_C") (pintype "passive"))
      (node (ref "LED62") (pin "A") (pinfunction "A_A") (pintype "passive"))
    )
    (net (code "65") (name "Net-(LED62-PadC)") (class "Default")
      (node (ref "LED62") (pin "C") (pinfunction "C_C") (pintype "passive"))
      (node (ref "LED63") (pin "A") (pinfunction "A_A") (pintype "passive"))
    )
    (net (code "66") (name "Net-(LED63-PadC)") (class "Default")
      (node (ref "LED63") (pin "C") (pinfunction "C_C") (pintype "passive"))
      (node (ref "LED64") (pin "A") (pinfunction "A_A") (pintype "passive"))
    )
    (net (code "67") (name "Net-(LED65-PadA)") (class "Default")
      (node (ref "LED65") (pin "A") (pinfunction "A_A") (pintype "passive"))
      (node (ref "R17") (pin "1") (pinfunction "1_1") (pintype "passive"))
    )
    (net (code "68") (name "Net-(LED65-PadC)") (class "Default")
      (node (ref "LED65") (pin "C") (pinfunction "C_C") (pintype "passive"))
      (node (ref "LED66") (pin "A") (pinfunction "A_A") (pintype "passive"))
    )
    (net (code "69") (name "Net-(LED66-PadC)") (class "Default")
      (node (ref "LED66") (pin "C") (pinfunction "C_C") (pintype "passive"))
      (node (ref "LED67") (pin "A") (pinfunction "A_A") (pintype "passive"))
    )
    (net (code "70") (name "Net-(LED67-PadC)") (class "Default")
      (node (ref "LED67") (pin "C") (pinfunction "C_C") (pintype "passive"))
      (node (ref "LED68") (pin "A") (pinfunction "A_A") (pintype "passive"))
    )
    (net (code "71") (name "Net-(LED69-PadA)") (class "Default")
      (node (ref "LED69") (pin "A") (pinfunction "A_A") (pintype "passive"))
      (node (ref "R18") (pin "1") (pinfunction "1_1") (pintype "passive"))
    )
    (net (code "72") (name "Net-(LED69-PadC)") (class "Default")
      (node (ref "LED69") (pin "C") (pinfunction "C_C") (pintype "passive"))
      (node (ref "LED70") (pin "A") (pinfunction "A_A") (pintype "passive"))
    )
    (net (code "73") (name "Net-(LED70-PadC)") (class "Default")
      (node (ref "LED70") (pin "C") (pinfunction "C_C") (pintype "passive"))
      (node (ref "LED71") (pin "A") (pinfunction "A_A") (pintype "passive"))
    )
    (net (code "74") (name "Net-(LED71-PadC)") (class "Default")
      (node (ref "LED71") (pin "C") (pinfunction "C_C") (pintype "passive"))
      (node (ref "LED72") (pin "A") (pinfunction "A_A") (pintype "passive"))
    )
    (net (code "75") (name "Net-(LED73-PadA)") (class "Default")
      (node (ref "LED73") (pin "A") (pinfunction "A_A") (pintype "passive"))
      (node (ref "R19") (pin "1") (pinfunction "1_1") (pintype "passive"))
    )
    (net (code "76") (name "Net-(LED73-PadC)") (class "Default")
      (node (ref "LED73") (pin "C") (pinfunction "C_C") (pintype "passive"))
      (node (ref "LED74") (pin "A") (pinfunction "A_A") (pintype "passive"))
    )
    (net (code "77") (name "Net-(LED74-PadC)") (class "Default")
      (node (ref "LED74") (pin "C") (pinfunction "C_C") (pintype "passive"))
      (node (ref "LED75") (pin "A") (pinfunction "A_A") (pintype "passive"))
    )
    (net (code "78") (name "Net-(LED75-PadC)") (class "Default")
      (node (ref "LED75") (pin "C") (pinfunction "C_C") (pintype "passive"))
      (node (ref "LED76") (pin "A") (pinfunction "A_A") (pintype "passive"))
    )
    (net (code "79") (name "Net-(LED77-PadA)") (class "Default")
      (node (ref "LED77") (pin "A") (pinfunction "A_A") (pintype "passive"))
      (node (ref "R20") (pin "1") (pinfunction "1_1") (pintype "passive"))
    )
    (net (code "80") (name "Net-(LED77-PadC)") (class "Default")
      (node (ref "LED77") (pin "C") (pinfunction "C_C") (pintype "passive"))
      (node (ref "LED78") (pin "A") (pinfunction "A_A") (pintype "passive"))
    )
    (net (code "81") (name "Net-(LED78-PadC)") (class "Default")
      (node (ref "LED78") (pin "C") (pinfunction "C_C") (pintype "passive"))
      (node (ref "LED79") (pin "A") (pinfunction "A_A") (pintype "passive"))
    )
    (net (code "82") (name "Net-(LED79-PadC)") (class "Default")
      (node (ref "LED79") (pin "C") (pinfunction "C_C") (pintype "passive"))
      (node (ref "LED80") (pin "A") (pinfunction "A_A") (pintype "passive"))
    )
    (net (code "83") (name "Net-(LED81-PadA)") (class "Default")
      (node (ref "LED81") (pin "A") (pinfunction "A_A") (pintype "passive"))
      (node (ref "R21") (pin "1") (pinfunction "1_1") (pintype "passive"))
    )
    (net (code "84") (name "Net-(LED81-PadC)") (class "Default")
      (node (ref "LED81") (pin "C") (pinfunction "C_C") (pintype "passive"))
      (node (ref "LED82") (pin "A") (pinfunction "A_A") (pintype "passive"))
    )
    (net (code "85") (name "Net-(LED82-PadC)") (class "Default")
      (node (ref "LED82") (pin "C") (pinfunction "C_C") (pintype "passive"))
      (node (ref "LED83") (pin "A") (pinfunction "A_A") (pintype "passive"))
    )
    (net (code "86") (name "Net-(LED83-PadC)") (class "Default")
      (node (ref "LED83") (pin "C") (pinfunction "C_C") (pintype "passive"))
      (node (ref "LED84") (pin "A") (pinfunction "A_A") (pintype "passive"))
    )
    (net (code "87") (name "Net-(LED85-PadA)") (class "Default")
      (node (ref "LED85") (pin "A") (pinfunction "A_A") (pintype "passive"))
      (node (ref "R22") (pin "1") (pinfunction "1_1") (pintype "passive"))
    )
    (net (code "88") (name "Net-(LED85-PadC)") (class "Default")
      (node (ref "LED85") (pin "C") (pinfunction "C_C") (pintype "passive"))
      (node (ref "LED86") (pin "A") (pinfunction "A_A") (pintype "passive"))
    )
    (net (code "89") (name "Net-(LED86-PadC)") (class "Default")
      (node (ref "LED86") (pin "C") (pinfunction "C_C") (pintype "passive"))
      (node (ref "LED87") (pin "A") (pinfunction "A_A") (pintype "passive"))
    )
    (net (code "90") (name "Net-(LED87-PadC)") (class "Default")
      (node (ref "LED87") (pin "C") (pinfunction "C_C") (pintype "passive"))
      (node (ref "LED88") (pin "A") (pinfunction "A_A") (pintype "passive"))
    )
    (net (code "91") (name "Net-(LED89-PadA)") (class "Default")
      (node (ref "LED89") (pin "A") (pinfunction "A_A") (pintype "passive"))
      (node (ref "R23") (pin "1") (pinfunction "1_1") (pintype "passive"))
    )
    (net (code "92") (name "Net-(LED89-PadC)") (class "Default")
      (node (ref "LED89") (pin "C") (pinfunction "C_C") (pintype "passive"))
      (node (ref "LED90") (pin "A") (pinfunction "A_A") (pintype "passive"))
    )
    (net (code "93") (name "Net-(LED90-PadC)") (class "Default")
      (node (ref "LED90") (pin "C") (pinfunction "C_C") (pintype "passive"))
      (node (ref "LED91") (pin "A") (pinfunction "A_A") (pintype "passive"))
    )
    (net (code "94") (name "Net-(LED91-PadC)") (class "Default")
      (node (ref "LED91") (pin "C") (pinfunction "C_C") (pintype "passive"))
      (node (ref "LED92") (pin "A") (pinfunction "A_A") (pintype "passive"))
    )
    (net (code "95") (name "Net-(LED93-PadA)") (class "Default")
      (node (ref "LED93") (pin "A") (pinfunction "A_A") (pintype "passive"))
      (node (ref "R24") (pin "1") (pinfunction "1_1") (pintype "passive"))
    )
    (net (code "96") (name "Net-(LED93-PadC)") (class "Default")
      (node (ref "LED93") (pin "C") (pinfunction "C_C") (pintype "passive"))
      (node (ref "LED94") (pin "A") (pinfunction "A_A") (pintype "passive"))
    )
    (net (code "97") (name "Net-(LED94-PadC)") (class "Default")
      (node (ref "LED94") (pin "C") (pinfunction "C_C") (pintype "passive"))
      (node (ref "LED95") (pin "A") (pinfunction "A_A") (pintype "passive"))
    )
    (net (code "98") (name "Net-(LED95-PadC)") (class "Default")
      (node (ref "LED95") (pin "C") (pinfunction "C_C") (pintype "passive"))
      (node (ref "LED96") (pin "A") (pinfunction "A_A") (pintype "passive"))
    )
    (net (code "99") (name "VIN") (class "Default")
      (node (ref "J1") (pin "1") (pinfunction "1_1") (pintype "passive"))
      (node (ref "J2") (pin "1") (pinfunction "1_1") (pintype "passive"))
      (node (ref "R1") (pin "2") (pinfunction "2_2") (pintype "passive"))
      (node (ref "R10") (pin "2") (pinfunction "2_2") (pintype "passive"))
      (node (ref "R11") (pin "2") (pinfunction "2_2") (pintype "passive"))
      (node (ref "R12") (pin "2") (pinfunction "2_2") (pintype "passive"))
      (node (ref "R13") (pin "2") (pinfunction "2_2") (pintype "passive"))
      (node (ref "R14") (pin "2") (pinfunction "2_2") (pintype "passive"))
      (node (ref "R15") (pin "2") (pinfunction "2_2") (pintype "passive"))
      (node (ref "R16") (pin "2") (pinfunction "2_2") (pintype "passive"))
      (node (ref "R17") (pin "2") (pinfunction "2_2") (pintype "passive"))
      (node (ref "R18") (pin "2") (pinfunction "2_2") (pintype "passive"))
      (node (ref "R19") (pin "2") (pinfunction "2_2") (pintype "passive"))
      (node (ref "R2") (pin "2") (pinfunction "2_2") (pintype "passive"))
      (node (ref "R20") (pin "2") (pinfunction "2_2") (pintype "passive"))
      (node (ref "R21") (pin "2") (pinfunction "2_2") (pintype "passive"))
      (node (ref "R22") (pin "2") (pinfunction "2_2") (pintype "passive"))
      (node (ref "R23") (pin "2") (pinfunction "2_2") (pintype "passive"))
      (node (ref "R24") (pin "2") (pinfunction "2_2") (pintype "passive"))
      (node (ref "R25") (pin "2") (pinfunction "2_2") (pintype "passive"))
      (node (ref "R3") (pin "2") (pinfunction "2_2") (pintype "passive"))
      (node (ref "R4") (pin "2") (pinfunction "2_2") (pintype "passive"))
      (node (ref "R5") (pin "2") (pinfunction "2_2") (pintype "passive"))
      (node (ref "R6") (pin "2") (pinfunction "2_2") (pintype "passive"))
      (node (ref "R7") (pin "2") (pinfunction "2_2") (pintype "passive"))
      (node (ref "R8") (pin "2") (pinfunction "2_2") (pintype "passive"))
      (node (ref "R9") (pin "2") (pinfunction "2_2") (pintype "passive"))
    )
  )
)
